# UD3_1_N_P_Gate_Driver-Zogger-Laptop.net
KiCad netlist of a schematic drawn in Altium Designer
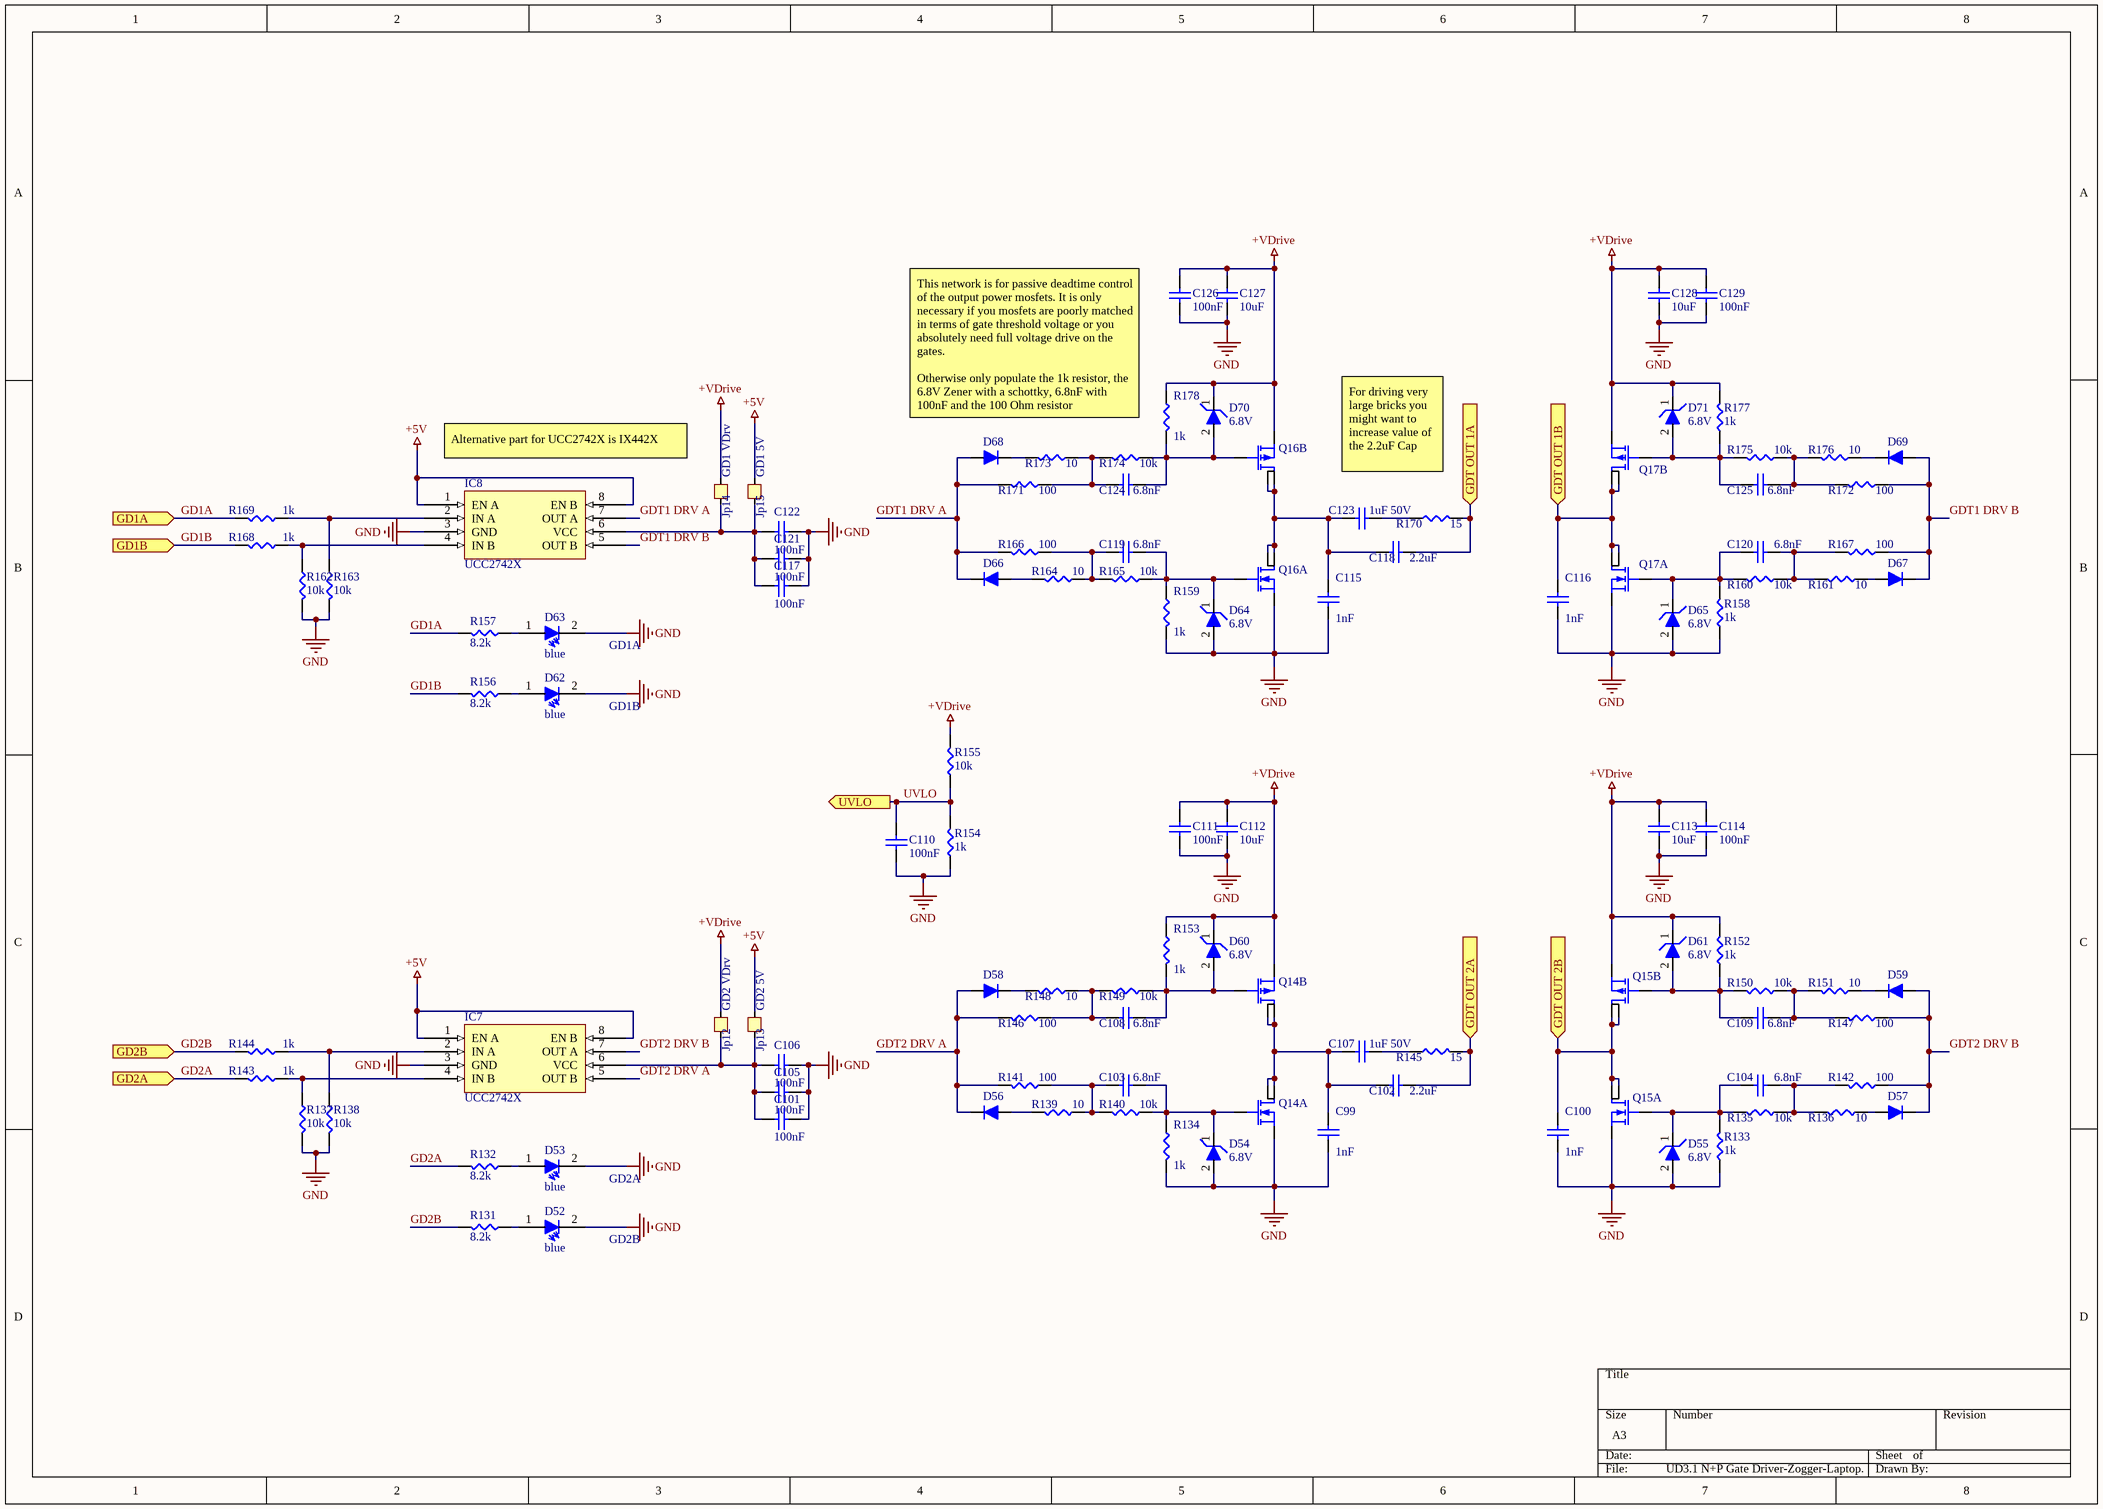
[diagram p0: UD3.1 N+P Gate Driver-Zogger-Laptop.SchDoc]

(export (version "E")
  (design (tool "Eeschema 10.0.6"))
  (components
    (comp (ref "C99") (value "1nF") (footprint "0603") (libsource (lib "stdLib") (part "Cap")))
    (comp (ref "C100") (value "1nF") (footprint "0603") (libsource (lib "stdLib") (part "Cap")))
    (comp (ref "C101") (value "100nF") (footprint "0603") (libsource (lib "stdLib") (part "Cap")))
    (comp (ref "C102") (value "2.2uF") (footprint "1210") (libsource (lib "stdLib") (part "Cap")))
    (comp (ref "C103") (value "6.8nF") (footprint "0603") (libsource (lib "stdLib") (part "Cap")))
    (comp (ref "C104") (value "6.8nF") (footprint "0603") (libsource (lib "stdLib") (part "Cap")))
    (comp (ref "C105") (value "100nF") (footprint "0603") (libsource (lib "stdLib") (part "Cap")))
    (comp (ref "C106") (value "100nF") (footprint "0603") (libsource (lib "stdLib") (part "Cap")))
    (comp (ref "C107") (value "1uF 50V") (footprint "1210") (libsource (lib "stdLib") (part "Cap")))
    (comp (ref "C108") (value "6.8nF") (footprint "0603") (libsource (lib "stdLib") (part "Cap")))
    (comp (ref "C109") (value "6.8nF") (footprint "0603") (libsource (lib "stdLib") (part "Cap")))
    (comp (ref "C110") (value "100nF") (footprint "0603") (libsource (lib "stdLib") (part "Cap")))
    (comp (ref "C111") (value "100nF") (footprint "0603") (libsource (lib "stdLib") (part "Cap")))
    (comp (ref "C112") (value "10uF") (footprint "0805") (libsource (lib "stdLib") (part "Cap")))
    (comp (ref "C113") (value "10uF") (footprint "0805") (libsource (lib "stdLib") (part "Cap")))
    (comp (ref "C114") (value "100nF") (footprint "0603") (libsource (lib "stdLib") (part "Cap")))
    (comp (ref "C115") (value "1nF") (footprint "0603") (libsource (lib "stdLib") (part "Cap")))
    (comp (ref "C116") (value "1nF") (footprint "0603") (libsource (lib "stdLib") (part "Cap")))
    (comp (ref "C117") (value "100nF") (footprint "0603") (libsource (lib "stdLib") (part "Cap")))
    (comp (ref "C118") (value "2.2uF") (footprint "1210") (libsource (lib "stdLib") (part "Cap")))
    (comp (ref "C119") (value "6.8nF") (footprint "0603") (libsource (lib "stdLib") (part "Cap")))
    (comp (ref "C120") (value "6.8nF") (footprint "0603") (libsource (lib "stdLib") (part "Cap")))
    (comp (ref "C121") (value "100nF") (footprint "0603") (libsource (lib "stdLib") (part "Cap")))
    (comp (ref "C122") (value "100nF") (footprint "0603") (libsource (lib "stdLib") (part "Cap")))
    (comp (ref "C123") (value "1uF 50V") (footprint "1210") (libsource (lib "stdLib") (part "Cap")))
    (comp (ref "C124") (value "6.8nF") (footprint "0603") (libsource (lib "stdLib") (part "Cap")))
    (comp (ref "C125") (value "6.8nF") (footprint "0603") (libsource (lib "stdLib") (part "Cap")))
    (comp (ref "C126") (value "100nF") (footprint "0603") (libsource (lib "stdLib") (part "Cap")))
    (comp (ref "C127") (value "10uF") (footprint "0805") (libsource (lib "stdLib") (part "Cap")))
    (comp (ref "C128") (value "10uF") (footprint "0805") (libsource (lib "stdLib") (part "Cap")))
    (comp (ref "C129") (value "100nF") (footprint "0603") (libsource (lib "stdLib") (part "Cap")))
    (comp (ref "D52")
      (value "blue")
      (footprint "1206 Reverse Mount")
      (description "Diode, but it lights up")
      (libsource (lib "stdLib") (part "LED"))
    )
    (comp (ref "D53")
      (value "blue")
      (footprint "1206 Reverse Mount")
      (description "Diode, but it lights up")
      (libsource (lib "stdLib") (part "LED"))
    )
    (comp (ref "D54") (value "6.8V") (footprint "SOD523") (libsource (lib "stdLib") (part "Diode Zener")))
    (comp (ref "D55") (value "6.8V") (footprint "SOD523") (libsource (lib "stdLib") (part "Diode Zener")))
    (comp (ref "D56")
      (value "Schottky 30V 100mA")
      (footprint "SOD523")
      (description "Cmon its a diode what more do I need to say?")
      (libsource (lib "stdLib") (part "Diode"))
    )
    (comp (ref "D57")
      (value "Schottky 30V 100mA")
      (footprint "SOD523")
      (description "Cmon its a diode what more do I need to say?")
      (libsource (lib "stdLib") (part "Diode"))
    )
    (comp (ref "D58")
      (value "Schottky 30V 100mA")
      (footprint "SOD523")
      (description "Cmon its a diode what more do I need to say?")
      (libsource (lib "stdLib") (part "Diode"))
    )
    (comp (ref "D59")
      (value "Schottky 30V 100mA")
      (footprint "SOD523")
      (description "Cmon its a diode what more do I need to say?")
      (libsource (lib "stdLib") (part "Diode"))
    )
    (comp (ref "D60") (value "6.8V") (footprint "SOD523") (libsource (lib "stdLib") (part "Diode Zener")))
    (comp (ref "D61") (value "6.8V") (footprint "SOD523") (libsource (lib "stdLib") (part "Diode Zener")))
    (comp (ref "D62")
      (value "blue")
      (footprint "1206 Reverse Mount")
      (description "Diode, but it lights up")
      (libsource (lib "stdLib") (part "LED"))
    )
    (comp (ref "D63")
      (value "blue")
      (footprint "1206 Reverse Mount")
      (description "Diode, but it lights up")
      (libsource (lib "stdLib") (part "LED"))
    )
    (comp (ref "D64") (value "6.8V") (footprint "SOD523") (libsource (lib "stdLib") (part "Diode Zener")))
    (comp (ref "D65") (value "6.8V") (footprint "SOD523") (libsource (lib "stdLib") (part "Diode Zener")))
    (comp (ref "D66")
      (value "Schottky 30V 100mA")
      (footprint "SOD523")
      (description "Cmon its a diode what more do I need to say?")
      (libsource (lib "stdLib") (part "Diode"))
    )
    (comp (ref "D67")
      (value "Schottky 30V 100mA")
      (footprint "SOD523")
      (description "Cmon its a diode what more do I need to say?")
      (libsource (lib "stdLib") (part "Diode"))
    )
    (comp (ref "D68")
      (value "Schottky 30V 100mA")
      (footprint "SOD523")
      (description "Cmon its a diode what more do I need to say?")
      (libsource (lib "stdLib") (part "Diode"))
    )
    (comp (ref "D69")
      (value "Schottky 30V 100mA")
      (footprint "SOD523")
      (description "Cmon its a diode what more do I need to say?")
      (libsource (lib "stdLib") (part "Diode"))
    )
    (comp (ref "D70") (value "6.8V") (footprint "SOD523") (libsource (lib "stdLib") (part "Diode Zener")))
    (comp (ref "D71") (value "6.8V") (footprint "SOD523") (libsource (lib "stdLib") (part "Diode Zener")))
    (comp (ref "IC7")
      (value "UCC2742X")
      (footprint "SOIC8")
      (description "Dual gate driver")
      (libsource (lib "stdLib") (part "UCC2742X"))
    )
    (comp (ref "IC8")
      (value "UCC2742X")
      (footprint "SOIC8")
      (description "Dual gate driver")
      (libsource (lib "stdLib") (part "UCC2742X"))
    )
    (comp (ref "Jp12")
      (value "GD2 VDrv")
      (footprint "PCB Jumper NO")
      (libsource (lib "stdLib") (part "Jumper"))
    )
    (comp (ref "Jp13")
      (value "GD2 5V")
      (footprint "PCB Jumper NO")
      (libsource (lib "stdLib") (part "Jumper"))
    )
    (comp (ref "Jp14")
      (value "GD1 VDrv")
      (footprint "PCB Jumper NO")
      (libsource (lib "stdLib") (part "Jumper"))
    )
    (comp (ref "Jp15")
      (value "GD1 5V")
      (footprint "PCB Jumper NO")
      (libsource (lib "stdLib") (part "Jumper"))
    )
    (comp (ref "Q14")
      (value "Mosfet 1N1P")
      (footprint "SO-8FL - Dual")
      (description "Dual Mosfet, one N & P channel resp.")
      (libsource (lib "stdLib") (part "Mosfet 1N1P"))
    )
    (comp (ref "Q15")
      (value "Mosfet 1N1P")
      (footprint "SO-8FL - Dual")
      (description "Dual Mosfet, one N & P channel resp.")
      (libsource (lib "stdLib") (part "Mosfet 1N1P"))
    )
    (comp (ref "Q16")
      (value "Mosfet 1N1P")
      (footprint "SO-8FL - Dual")
      (description "Dual Mosfet, one N & P channel resp.")
      (libsource (lib "stdLib") (part "Mosfet 1N1P"))
    )
    (comp (ref "Q17")
      (value "Mosfet 1N1P")
      (footprint "SO-8FL - Dual")
      (description "Dual Mosfet, one N & P channel resp.")
      (libsource (lib "stdLib") (part "Mosfet 1N1P"))
    )
    (comp (ref "R131") (value "8.2k") (footprint "0603") (libsource (lib "stdLib") (part "Resistor")))
    (comp (ref "R132") (value "8.2k") (footprint "0603") (libsource (lib "stdLib") (part "Resistor")))
    (comp (ref "R133") (value "1k") (footprint "0603") (libsource (lib "stdLib") (part "Resistor")))
    (comp (ref "R134") (value "1k") (footprint "0603") (libsource (lib "stdLib") (part "Resistor")))
    (comp (ref "R135") (value "10k") (footprint "0603") (libsource (lib "stdLib") (part "Resistor")))
    (comp (ref "R136") (value "10") (footprint "0603") (libsource (lib "stdLib") (part "Resistor")))
    (comp (ref "R137") (value "10k") (footprint "0603") (libsource (lib "stdLib") (part "Resistor")))
    (comp (ref "R138") (value "10k") (footprint "0603") (libsource (lib "stdLib") (part "Resistor")))
    (comp (ref "R139") (value "10") (footprint "0603") (libsource (lib "stdLib") (part "Resistor")))
    (comp (ref "R140") (value "10k") (footprint "0603") (libsource (lib "stdLib") (part "Resistor")))
    (comp (ref "R141") (value "100") (footprint "0603") (libsource (lib "stdLib") (part "Resistor")))
    (comp (ref "R142") (value "100") (footprint "0603") (libsource (lib "stdLib") (part "Resistor")))
    (comp (ref "R143") (value "1k") (footprint "0603") (libsource (lib "stdLib") (part "Resistor")))
    (comp (ref "R144") (value "1k") (footprint "0603") (libsource (lib "stdLib") (part "Resistor")))
    (comp (ref "R145") (value "15") (footprint "1210") (libsource (lib "stdLib") (part "Resistor")))
    (comp (ref "R146") (value "100") (footprint "0603") (libsource (lib "stdLib") (part "Resistor")))
    (comp (ref "R147") (value "100") (footprint "0603") (libsource (lib "stdLib") (part "Resistor")))
    (comp (ref "R148") (value "10") (footprint "0603") (libsource (lib "stdLib") (part "Resistor")))
    (comp (ref "R149") (value "10k") (footprint "0603") (libsource (lib "stdLib") (part "Resistor")))
    (comp (ref "R150") (value "10k") (footprint "0603") (libsource (lib "stdLib") (part "Resistor")))
    (comp (ref "R151") (value "10") (footprint "0603") (libsource (lib "stdLib") (part "Resistor")))
    (comp (ref "R152") (value "1k") (footprint "0603") (libsource (lib "stdLib") (part "Resistor")))
    (comp (ref "R153") (value "1k") (footprint "0603") (libsource (lib "stdLib") (part "Resistor")))
    (comp (ref "R154") (value "1k") (footprint "0603") (libsource (lib "stdLib") (part "Resistor")))
    (comp (ref "R155") (value "10k") (footprint "0603") (libsource (lib "stdLib") (part "Resistor")))
    (comp (ref "R156") (value "8.2k") (footprint "0603") (libsource (lib "stdLib") (part "Resistor")))
    (comp (ref "R157") (value "8.2k") (footprint "0603") (libsource (lib "stdLib") (part "Resistor")))
    (comp (ref "R158") (value "1k") (footprint "0603") (libsource (lib "stdLib") (part "Resistor")))
    (comp (ref "R159") (value "1k") (footprint "0603") (libsource (lib "stdLib") (part "Resistor")))
    (comp (ref "R160") (value "10k") (footprint "0603") (libsource (lib "stdLib") (part "Resistor")))
    (comp (ref "R161") (value "10") (footprint "0603") (libsource (lib "stdLib") (part "Resistor")))
    (comp (ref "R162") (value "10k") (footprint "0603") (libsource (lib "stdLib") (part "Resistor")))
    (comp (ref "R163") (value "10k") (footprint "0603") (libsource (lib "stdLib") (part "Resistor")))
    (comp (ref "R164") (value "10") (footprint "0603") (libsource (lib "stdLib") (part "Resistor")))
    (comp (ref "R165") (value "10k") (footprint "0603") (libsource (lib "stdLib") (part "Resistor")))
    (comp (ref "R166") (value "100") (footprint "0603") (libsource (lib "stdLib") (part "Resistor")))
    (comp (ref "R167") (value "100") (footprint "0603") (libsource (lib "stdLib") (part "Resistor")))
    (comp (ref "R168") (value "1k") (footprint "0603") (libsource (lib "stdLib") (part "Resistor")))
    (comp (ref "R169") (value "1k") (footprint "0603") (libsource (lib "stdLib") (part "Resistor")))
    (comp (ref "R170") (value "15") (footprint "1210") (libsource (lib "stdLib") (part "Resistor")))
    (comp (ref "R171") (value "100") (footprint "0603") (libsource (lib "stdLib") (part "Resistor")))
    (comp (ref "R172") (value "100") (footprint "0603") (libsource (lib "stdLib") (part "Resistor")))
    (comp (ref "R173") (value "10") (footprint "0603") (libsource (lib "stdLib") (part "Resistor")))
    (comp (ref "R174") (value "10k") (footprint "0603") (libsource (lib "stdLib") (part "Resistor")))
    (comp (ref "R175") (value "10k") (footprint "0603") (libsource (lib "stdLib") (part "Resistor")))
    (comp (ref "R176") (value "10") (footprint "0603") (libsource (lib "stdLib") (part "Resistor")))
    (comp (ref "R177") (value "1k") (footprint "0603") (libsource (lib "stdLib") (part "Resistor")))
    (comp (ref "R178") (value "1k") (footprint "0603") (libsource (lib "stdLib") (part "Resistor")))
  )
  (nets
    (net (code "1") (name "+5V") (class "Default")
      (node (ref "IC7") (pin "1") (pinfunction "EN_A_1") (pintype "input"))
      (node (ref "IC7") (pin "8") (pinfunction "EN_B_8") (pintype "input"))
      (node (ref "IC8") (pin "1") (pinfunction "EN_A_1") (pintype "input"))
      (node (ref "IC8") (pin "8") (pinfunction "EN_B_8") (pintype "input"))
      (node (ref "Jp13") (pin "2") (pinfunction "2_2") (pintype "passive"))
      (node (ref "Jp15") (pin "2") (pinfunction "2_2") (pintype "passive"))
    )
    (net (code "2") (name "+VDrive") (class "Default")
      (node (ref "C111") (pin "2") (pinfunction "2_2") (pintype "passive"))
      (node (ref "C112") (pin "2") (pinfunction "2_2") (pintype "passive"))
      (node (ref "C113") (pin "2") (pinfunction "2_2") (pintype "passive"))
      (node (ref "C114") (pin "2") (pinfunction "2_2") (pintype "passive"))
      (node (ref "C126") (pin "2") (pinfunction "2_2") (pintype "passive"))
      (node (ref "C127") (pin "2") (pinfunction "2_2") (pintype "passive"))
      (node (ref "C128") (pin "2") (pinfunction "2_2") (pintype "passive"))
      (node (ref "C129") (pin "2") (pinfunction "2_2") (pintype "passive"))
      (node (ref "D60") (pin "1") (pintype "passive"))
      (node (ref "D61") (pin "1") (pintype "passive"))
      (node (ref "D70") (pin "1") (pintype "passive"))
      (node (ref "D71") (pin "1") (pintype "passive"))
      (node (ref "Jp12") (pin "2") (pinfunction "2_2") (pintype "passive"))
      (node (ref "Jp14") (pin "2") (pinfunction "2_2") (pintype "passive"))
      (node (ref "Q14") (pin "Sp") (pinfunction "Sp_Sp") (pintype "passive"))
      (node (ref "Q15") (pin "Sp") (pinfunction "Sp_Sp") (pintype "passive"))
      (node (ref "Q16") (pin "Sp") (pinfunction "Sp_Sp") (pintype "passive"))
      (node (ref "Q17") (pin "Sp") (pinfunction "Sp_Sp") (pintype "passive"))
      (node (ref "R152") (pin "2") (pinfunction "2_2") (pintype "passive"))
      (node (ref "R153") (pin "2") (pinfunction "2_2") (pintype "passive"))
      (node (ref "R155") (pin "1") (pinfunction "1_1") (pintype "passive"))
      (node (ref "R177") (pin "2") (pinfunction "2_2") (pintype "passive"))
      (node (ref "R178") (pin "2") (pinfunction "2_2") (pintype "passive"))
    )
    (net (code "3") (name "/GD1A") (class "Default")
      (node (ref "R157") (pin "1") (pinfunction "1_1") (pintype "passive"))
      (node (ref "R169") (pin "1") (pinfunction "1_1") (pintype "passive"))
    )
    (net (code "4") (name "/GD1B") (class "Default")
      (node (ref "R156") (pin "1") (pinfunction "1_1") (pintype "passive"))
      (node (ref "R168") (pin "1") (pinfunction "1_1") (pintype "passive"))
    )
    (net (code "5") (name "/GD2A") (class "Default")
      (node (ref "R132") (pin "1") (pinfunction "1_1") (pintype "passive"))
      (node (ref "R143") (pin "1") (pinfunction "1_1") (pintype "passive"))
    )
    (net (code "6") (name "/GD2B") (class "Default")
      (node (ref "R131") (pin "1") (pinfunction "1_1") (pintype "passive"))
      (node (ref "R144") (pin "1") (pinfunction "1_1") (pintype "passive"))
    )
    (net (code "7") (name "/GDT OUT 1A") (class "Default")
      (node (ref "C118") (pin "2") (pinfunction "2_2") (pintype "passive"))
      (node (ref "R170") (pin "2") (pinfunction "2_2") (pintype "passive"))
    )
    (net (code "8") (name "/GDT OUT 1B") (class "Default")
      (node (ref "C116") (pin "2") (pinfunction "2_2") (pintype "passive"))
      (node (ref "Q17") (pin "Dn1") (pinfunction "Dn1_Dn1") (pintype "passive"))
      (node (ref "Q17") (pin "Dn2") (pinfunction "Dn2_Dn2") (pintype "passive"))
      (node (ref "Q17") (pin "Dp1") (pinfunction "Dp1_Dp1") (pintype "passive"))
      (node (ref "Q17") (pin "Dp2") (pinfunction "Dp2_Dp2") (pintype "passive"))
    )
    (net (code "9") (name "/GDT OUT 2A") (class "Default")
      (node (ref "C102") (pin "2") (pinfunction "2_2") (pintype "passive"))
      (node (ref "R145") (pin "2") (pinfunction "2_2") (pintype "passive"))
    )
    (net (code "10") (name "/GDT OUT 2B") (class "Default")
      (node (ref "C100") (pin "2") (pinfunction "2_2") (pintype "passive"))
      (node (ref "Q15") (pin "Dn1") (pinfunction "Dn1_Dn1") (pintype "passive"))
      (node (ref "Q15") (pin "Dn2") (pinfunction "Dn2_Dn2") (pintype "passive"))
      (node (ref "Q15") (pin "Dp1") (pinfunction "Dp1_Dp1") (pintype "passive"))
      (node (ref "Q15") (pin "Dp2") (pinfunction "Dp2_Dp2") (pintype "passive"))
    )
    (net (code "11") (name "/GDT1 DRV A") (class "Default")
      (node (ref "D66") (pin "2") (pintype "passive"))
      (node (ref "D68") (pin "1") (pintype "passive"))
      (node (ref "IC8") (pin "7") (pinfunction "OUT_A_7") (pintype "input"))
      (node (ref "R166") (pin "1") (pinfunction "1_1") (pintype "passive"))
      (node (ref "R171") (pin "1") (pinfunction "1_1") (pintype "passive"))
    )
    (net (code "12") (name "/GDT1 DRV B") (class "Default")
      (node (ref "D67") (pin "2") (pintype "passive"))
      (node (ref "D69") (pin "1") (pintype "passive"))
      (node (ref "IC8") (pin "5") (pinfunction "OUT_B_5") (pintype "input"))
      (node (ref "R167") (pin "1") (pinfunction "1_1") (pintype "passive"))
      (node (ref "R172") (pin "1") (pinfunction "1_1") (pintype "passive"))
    )
    (net (code "13") (name "/GDT2 DRV A") (class "Default")
      (node (ref "D56") (pin "2") (pintype "passive"))
      (node (ref "D58") (pin "1") (pintype "passive"))
      (node (ref "IC7") (pin "5") (pinfunction "OUT_B_5") (pintype "input"))
      (node (ref "R141") (pin "1") (pinfunction "1_1") (pintype "passive"))
      (node (ref "R146") (pin "1") (pinfunction "1_1") (pintype "passive"))
    )
    (net (code "14") (name "/GDT2 DRV B") (class "Default")
      (node (ref "D57") (pin "2") (pintype "passive"))
      (node (ref "D59") (pin "1") (pintype "passive"))
      (node (ref "IC7") (pin "7") (pinfunction "OUT_A_7") (pintype "input"))
      (node (ref "R142") (pin "1") (pinfunction "1_1") (pintype "passive"))
      (node (ref "R147") (pin "1") (pinfunction "1_1") (pintype "passive"))
    )
    (net (code "15") (name "/UVLO") (class "Default")
      (node (ref "C110") (pin "2") (pinfunction "2_2") (pintype "passive"))
      (node (ref "R154") (pin "1") (pinfunction "1_1") (pintype "passive"))
      (node (ref "R155") (pin "2") (pinfunction "2_2") (pintype "passive"))
    )
    (net (code "16") (name "GND") (class "Default")
      (node (ref "C100") (pin "1") (pinfunction "1_1") (pintype "passive"))
      (node (ref "C101") (pin "2") (pinfunction "2_2") (pintype "passive"))
      (node (ref "C105") (pin "2") (pinfunction "2_2") (pintype "passive"))
      (node (ref "C106") (pin "2") (pinfunction "2_2") (pintype "passive"))
      (node (ref "C110") (pin "1") (pinfunction "1_1") (pintype "passive"))
      (node (ref "C111") (pin "1") (pinfunction "1_1") (pintype "passive"))
      (node (ref "C112") (pin "1") (pinfunction "1_1") (pintype "passive"))
      (node (ref "C113") (pin "1") (pinfunction "1_1") (pintype "passive"))
      (node (ref "C114") (pin "1") (pinfunction "1_1") (pintype "passive"))
      (node (ref "C115") (pin "1") (pinfunction "1_1") (pintype "passive"))
      (node (ref "C116") (pin "1") (pinfunction "1_1") (pintype "passive"))
      (node (ref "C117") (pin "2") (pinfunction "2_2") (pintype "passive"))
      (node (ref "C121") (pin "2") (pinfunction "2_2") (pintype "passive"))
      (node (ref "C122") (pin "2") (pinfunction "2_2") (pintype "passive"))
      (node (ref "C126") (pin "1") (pinfunction "1_1") (pintype "passive"))
      (node (ref "C127") (pin "1") (pinfunction "1_1") (pintype "passive"))
      (node (ref "C128") (pin "1") (pinfunction "1_1") (pintype "passive"))
      (node (ref "C129") (pin "1") (pinfunction "1_1") (pintype "passive"))
      (node (ref "C99") (pin "1") (pinfunction "1_1") (pintype "passive"))
      (node (ref "D52") (pin "2") (pintype "passive"))
      (node (ref "D53") (pin "2") (pintype "passive"))
      (node (ref "D54") (pin "2") (pintype "passive"))
      (node (ref "D55") (pin "2") (pintype "passive"))
      (node (ref "D62") (pin "2") (pintype "passive"))
      (node (ref "D63") (pin "2") (pintype "passive"))
      (node (ref "D64") (pin "2") (pintype "passive"))
      (node (ref "D65") (pin "2") (pintype "passive"))
      (node (ref "IC7") (pin "3") (pinfunction "GND_3") (pintype "input"))
      (node (ref "IC8") (pin "3") (pinfunction "GND_3") (pintype "input"))
      (node (ref "Q14") (pin "Sn") (pinfunction "Sn_Sn") (pintype "passive"))
      (node (ref "Q15") (pin "Sn") (pinfunction "Sn_Sn") (pintype "passive"))
      (node (ref "Q16") (pin "Sn") (pinfunction "Sn_Sn") (pintype "passive"))
      (node (ref "Q17") (pin "Sn") (pinfunction "Sn_Sn") (pintype "passive"))
      (node (ref "R133") (pin "1") (pinfunction "1_1") (pintype "passive"))
      (node (ref "R134") (pin "1") (pinfunction "1_1") (pintype "passive"))
      (node (ref "R137") (pin "1") (pinfunction "1_1") (pintype "passive"))
      (node (ref "R138") (pin "1") (pinfunction "1_1") (pintype "passive"))
      (node (ref "R154") (pin "2") (pinfunction "2_2") (pintype "passive"))
      (node (ref "R158") (pin "1") (pinfunction "1_1") (pintype "passive"))
      (node (ref "R159") (pin "1") (pinfunction "1_1") (pintype "passive"))
      (node (ref "R162") (pin "1") (pinfunction "1_1") (pintype "passive"))
      (node (ref "R163") (pin "1") (pinfunction "1_1") (pintype "passive"))
    )
    (net (code "17") (name "Net-(C102-Pad1)") (class "Default")
      (node (ref "C102") (pin "1") (pinfunction "1_1") (pintype "passive"))
      (node (ref "C107") (pin "1") (pinfunction "1_1") (pintype "passive"))
      (node (ref "C99") (pin "2") (pinfunction "2_2") (pintype "passive"))
      (node (ref "Q14") (pin "Dn1") (pinfunction "Dn1_Dn1") (pintype "passive"))
      (node (ref "Q14") (pin "Dn2") (pinfunction "Dn2_Dn2") (pintype "passive"))
      (node (ref "Q14") (pin "Dp1") (pinfunction "Dp1_Dp1") (pintype "passive"))
      (node (ref "Q14") (pin "Dp2") (pinfunction "Dp2_Dp2") (pintype "passive"))
    )
    (net (code "18") (name "Net-(C103-Pad1)") (class "Default")
      (node (ref "C103") (pin "1") (pinfunction "1_1") (pintype "passive"))
      (node (ref "R139") (pin "2") (pinfunction "2_2") (pintype "passive"))
      (node (ref "R140") (pin "1") (pinfunction "1_1") (pintype "passive"))
      (node (ref "R141") (pin "2") (pinfunction "2_2") (pintype "passive"))
    )
    (net (code "19") (name "Net-(C103-Pad2)") (class "Default")
      (node (ref "C103") (pin "2") (pinfunction "2_2") (pintype "passive"))
      (node (ref "D54") (pin "1") (pintype "passive"))
      (node (ref "Q14") (pin "Gn") (pinfunction "Gn_Gn") (pintype "passive"))
      (node (ref "R134") (pin "2") (pinfunction "2_2") (pintype "passive"))
      (node (ref "R140") (pin "2") (pinfunction "2_2") (pintype "passive"))
    )
    (net (code "20") (name "Net-(C104-Pad1)") (class "Default")
      (node (ref "C104") (pin "1") (pinfunction "1_1") (pintype "passive"))
      (node (ref "R135") (pin "1") (pinfunction "1_1") (pintype "passive"))
      (node (ref "R136") (pin "2") (pinfunction "2_2") (pintype "passive"))
      (node (ref "R142") (pin "2") (pinfunction "2_2") (pintype "passive"))
    )
    (net (code "21") (name "Net-(C104-Pad2)") (class "Default")
      (node (ref "C104") (pin "2") (pinfunction "2_2") (pintype "passive"))
      (node (ref "D55") (pin "1") (pintype "passive"))
      (node (ref "Q15") (pin "Gn") (pinfunction "Gn_Gn") (pintype "passive"))
      (node (ref "R133") (pin "2") (pinfunction "2_2") (pintype "passive"))
      (node (ref "R135") (pin "2") (pinfunction "2_2") (pintype "passive"))
    )
    (net (code "22") (name "Net-(C107-Pad2)") (class "Default")
      (node (ref "C107") (pin "2") (pinfunction "2_2") (pintype "passive"))
      (node (ref "R145") (pin "1") (pinfunction "1_1") (pintype "passive"))
    )
    (net (code "23") (name "Net-(C108-Pad1)") (class "Default")
      (node (ref "C108") (pin "1") (pinfunction "1_1") (pintype "passive"))
      (node (ref "R146") (pin "2") (pinfunction "2_2") (pintype "passive"))
      (node (ref "R148") (pin "2") (pinfunction "2_2") (pintype "passive"))
      (node (ref "R149") (pin "1") (pinfunction "1_1") (pintype "passive"))
    )
    (net (code "24") (name "Net-(C108-Pad2)") (class "Default")
      (node (ref "C108") (pin "2") (pinfunction "2_2") (pintype "passive"))
      (node (ref "D60") (pin "2") (pintype "passive"))
      (node (ref "Q14") (pin "Gp") (pinfunction "Gp_Gp") (pintype "passive"))
      (node (ref "R149") (pin "2") (pinfunction "2_2") (pintype "passive"))
      (node (ref "R153") (pin "1") (pinfunction "1_1") (pintype "passive"))
    )
    (net (code "25") (name "Net-(C109-Pad1)") (class "Default")
      (node (ref "C109") (pin "1") (pinfunction "1_1") (pintype "passive"))
      (node (ref "R147") (pin "2") (pinfunction "2_2") (pintype "passive"))
      (node (ref "R150") (pin "1") (pinfunction "1_1") (pintype "passive"))
      (node (ref "R151") (pin "2") (pinfunction "2_2") (pintype "passive"))
    )
    (net (code "26") (name "Net-(C109-Pad2)") (class "Default")
      (node (ref "C109") (pin "2") (pinfunction "2_2") (pintype "passive"))
      (node (ref "D61") (pin "2") (pintype "passive"))
      (node (ref "Q15") (pin "Gp") (pinfunction "Gp_Gp") (pintype "passive"))
      (node (ref "R150") (pin "2") (pinfunction "2_2") (pintype "passive"))
      (node (ref "R152") (pin "1") (pinfunction "1_1") (pintype "passive"))
    )
    (net (code "27") (name "Net-(C115-Pad2)") (class "Default")
      (node (ref "C115") (pin "2") (pinfunction "2_2") (pintype "passive"))
      (node (ref "C118") (pin "1") (pinfunction "1_1") (pintype "passive"))
      (node (ref "C123") (pin "1") (pinfunction "1_1") (pintype "passive"))
      (node (ref "Q16") (pin "Dn1") (pinfunction "Dn1_Dn1") (pintype "passive"))
      (node (ref "Q16") (pin "Dn2") (pinfunction "Dn2_Dn2") (pintype "passive"))
      (node (ref "Q16") (pin "Dp1") (pinfunction "Dp1_Dp1") (pintype "passive"))
      (node (ref "Q16") (pin "Dp2") (pinfunction "Dp2_Dp2") (pintype "passive"))
    )
    (net (code "28") (name "Net-(C119-Pad1)") (class "Default")
      (node (ref "C119") (pin "1") (pinfunction "1_1") (pintype "passive"))
      (node (ref "R164") (pin "2") (pinfunction "2_2") (pintype "passive"))
      (node (ref "R165") (pin "1") (pinfunction "1_1") (pintype "passive"))
      (node (ref "R166") (pin "2") (pinfunction "2_2") (pintype "passive"))
    )
    (net (code "29") (name "Net-(C119-Pad2)") (class "Default")
      (node (ref "C119") (pin "2") (pinfunction "2_2") (pintype "passive"))
      (node (ref "D64") (pin "1") (pintype "passive"))
      (node (ref "Q16") (pin "Gn") (pinfunction "Gn_Gn") (pintype "passive"))
      (node (ref "R159") (pin "2") (pinfunction "2_2") (pintype "passive"))
      (node (ref "R165") (pin "2") (pinfunction "2_2") (pintype "passive"))
    )
    (net (code "30") (name "Net-(C120-Pad1)") (class "Default")
      (node (ref "C120") (pin "1") (pinfunction "1_1") (pintype "passive"))
      (node (ref "R160") (pin "1") (pinfunction "1_1") (pintype "passive"))
      (node (ref "R161") (pin "2") (pinfunction "2_2") (pintype "passive"))
      (node (ref "R167") (pin "2") (pinfunction "2_2") (pintype "passive"))
    )
    (net (code "31") (name "Net-(C120-Pad2)") (class "Default")
      (node (ref "C120") (pin "2") (pinfunction "2_2") (pintype "passive"))
      (node (ref "D65") (pin "1") (pintype "passive"))
      (node (ref "Q17") (pin "Gn") (pinfunction "Gn_Gn") (pintype "passive"))
      (node (ref "R158") (pin "2") (pinfunction "2_2") (pintype "passive"))
      (node (ref "R160") (pin "2") (pinfunction "2_2") (pintype "passive"))
    )
    (net (code "32") (name "Net-(C123-Pad2)") (class "Default")
      (node (ref "C123") (pin "2") (pinfunction "2_2") (pintype "passive"))
      (node (ref "R170") (pin "1") (pinfunction "1_1") (pintype "passive"))
    )
    (net (code "33") (name "Net-(C124-Pad1)") (class "Default")
      (node (ref "C124") (pin "1") (pinfunction "1_1") (pintype "passive"))
      (node (ref "R171") (pin "2") (pinfunction "2_2") (pintype "passive"))
      (node (ref "R173") (pin "2") (pinfunction "2_2") (pintype "passive"))
      (node (ref "R174") (pin "1") (pinfunction "1_1") (pintype "passive"))
    )
    (net (code "34") (name "Net-(C124-Pad2)") (class "Default")
      (node (ref "C124") (pin "2") (pinfunction "2_2") (pintype "passive"))
      (node (ref "D70") (pin "2") (pintype "passive"))
      (node (ref "Q16") (pin "Gp") (pinfunction "Gp_Gp") (pintype "passive"))
      (node (ref "R174") (pin "2") (pinfunction "2_2") (pintype "passive"))
      (node (ref "R178") (pin "1") (pinfunction "1_1") (pintype "passive"))
    )
    (net (code "35") (name "Net-(C125-Pad1)") (class "Default")
      (node (ref "C125") (pin "1") (pinfunction "1_1") (pintype "passive"))
      (node (ref "R172") (pin "2") (pinfunction "2_2") (pintype "passive"))
      (node (ref "R175") (pin "1") (pinfunction "1_1") (pintype "passive"))
      (node (ref "R176") (pin "2") (pinfunction "2_2") (pintype "passive"))
    )
    (net (code "36") (name "Net-(C125-Pad2)") (class "Default")
      (node (ref "C125") (pin "2") (pinfunction "2_2") (pintype "passive"))
      (node (ref "D71") (pin "2") (pintype "passive"))
      (node (ref "Q17") (pin "Gp") (pinfunction "Gp_Gp") (pintype "passive"))
      (node (ref "R175") (pin "2") (pinfunction "2_2") (pintype "passive"))
      (node (ref "R177") (pin "1") (pinfunction "1_1") (pintype "passive"))
    )
    (net (code "37") (name "Net-(D52-Pad1)") (class "Default")
      (node (ref "D52") (pin "1") (pintype "passive"))
      (node (ref "R131") (pin "2") (pinfunction "2_2") (pintype "passive"))
    )
    (net (code "38") (name "Net-(D53-Pad1)") (class "Default")
      (node (ref "D53") (pin "1") (pintype "passive"))
      (node (ref "R132") (pin "2") (pinfunction "2_2") (pintype "passive"))
    )
    (net (code "39") (name "Net-(D56-Pad1)") (class "Default")
      (node (ref "D56") (pin "1") (pintype "passive"))
      (node (ref "R139") (pin "1") (pinfunction "1_1") (pintype "passive"))
    )
    (net (code "40") (name "Net-(D57-Pad1)") (class "Default")
      (node (ref "D57") (pin "1") (pintype "passive"))
      (node (ref "R136") (pin "1") (pinfunction "1_1") (pintype "passive"))
    )
    (net (code "41") (name "Net-(D58-Pad2)") (class "Default")
      (node (ref "D58") (pin "2") (pintype "passive"))
      (node (ref "R148") (pin "1") (pinfunction "1_1") (pintype "passive"))
    )
    (net (code "42") (name "Net-(D59-Pad2)") (class "Default")
      (node (ref "D59") (pin "2") (pintype "passive"))
      (node (ref "R151") (pin "1") (pinfunction "1_1") (pintype "passive"))
    )
    (net (code "43") (name "Net-(D62-Pad1)") (class "Default")
      (node (ref "D62") (pin "1") (pintype "passive"))
      (node (ref "R156") (pin "2") (pinfunction "2_2") (pintype "passive"))
    )
    (net (code "44") (name "Net-(D63-Pad1)") (class "Default")
      (node (ref "D63") (pin "1") (pintype "passive"))
      (node (ref "R157") (pin "2") (pinfunction "2_2") (pintype "passive"))
    )
    (net (code "45") (name "Net-(D66-Pad1)") (class "Default")
      (node (ref "D66") (pin "1") (pintype "passive"))
      (node (ref "R164") (pin "1") (pinfunction "1_1") (pintype "passive"))
    )
    (net (code "46") (name "Net-(D67-Pad1)") (class "Default")
      (node (ref "D67") (pin "1") (pintype "passive"))
      (node (ref "R161") (pin "1") (pinfunction "1_1") (pintype "passive"))
    )
    (net (code "47") (name "Net-(D68-Pad2)") (class "Default")
      (node (ref "D68") (pin "2") (pintype "passive"))
      (node (ref "R173") (pin "1") (pinfunction "1_1") (pintype "passive"))
    )
    (net (code "48") (name "Net-(D69-Pad2)") (class "Default")
      (node (ref "D69") (pin "2") (pintype "passive"))
      (node (ref "R176") (pin "1") (pinfunction "1_1") (pintype "passive"))
    )
    (net (code "49") (name "Net-(IC7-IN_A)") (class "Default")
      (node (ref "IC7") (pin "2") (pinfunction "IN_A_2") (pintype "input"))
      (node (ref "R138") (pin "2") (pinfunction "2_2") (pintype "passive"))
      (node (ref "R144") (pin "2") (pinfunction "2_2") (pintype "passive"))
    )
    (net (code "50") (name "Net-(IC7-IN_B)") (class "Default")
      (node (ref "IC7") (pin "4") (pinfunction "IN_B_4") (pintype "input"))
      (node (ref "R137") (pin "2") (pinfunction "2_2") (pintype "passive"))
      (node (ref "R143") (pin "2") (pinfunction "2_2") (pintype "passive"))
    )
    (net (code "51") (name "Net-(IC7-VCC)") (class "Default")
      (node (ref "C101") (pin "1") (pinfunction "1_1") (pintype "passive"))
      (node (ref "C105") (pin "1") (pinfunction "1_1") (pintype "passive"))
      (node (ref "C106") (pin "1") (pinfunction "1_1") (pintype "passive"))
      (node (ref "IC7") (pin "6") (pinfunction "VCC_6") (pintype "input"))
      (node (ref "Jp12") (pin "1") (pinfunction "1_1") (pintype "passive"))
      (node (ref "Jp13") (pin "1") (pinfunction "1_1") (pintype "passive"))
    )
    (net (code "52") (name "Net-(IC8-IN_A)") (class "Default")
      (node (ref "IC8") (pin "2") (pinfunction "IN_A_2") (pintype "input"))
      (node (ref "R163") (pin "2") (pinfunction "2_2") (pintype "passive"))
      (node (ref "R169") (pin "2") (pinfunction "2_2") (pintype "passive"))
    )
    (net (code "53") (name "Net-(IC8-IN_B)") (class "Default")
      (node (ref "IC8") (pin "4") (pinfunction "IN_B_4") (pintype "input"))
      (node (ref "R162") (pin "2") (pinfunction "2_2") (pintype "passive"))
      (node (ref "R168") (pin "2") (pinfunction "2_2") (pintype "passive"))
    )
    (net (code "54") (name "Net-(IC8-VCC)") (class "Default")
      (node (ref "C117") (pin "1") (pinfunction "1_1") (pintype "passive"))
      (node (ref "C121") (pin "1") (pinfunction "1_1") (pintype "passive"))
      (node (ref "C122") (pin "1") (pinfunction "1_1") (pintype "passive"))
      (node (ref "IC8") (pin "6") (pinfunction "VCC_6") (pintype "input"))
      (node (ref "Jp14") (pin "1") (pinfunction "1_1") (pintype "passive"))
      (node (ref "Jp15") (pin "1") (pinfunction "1_1") (pintype "passive"))
    )
  )
)
